# cookie.net
KiCad netlist of a schematic drawn in EAGLE
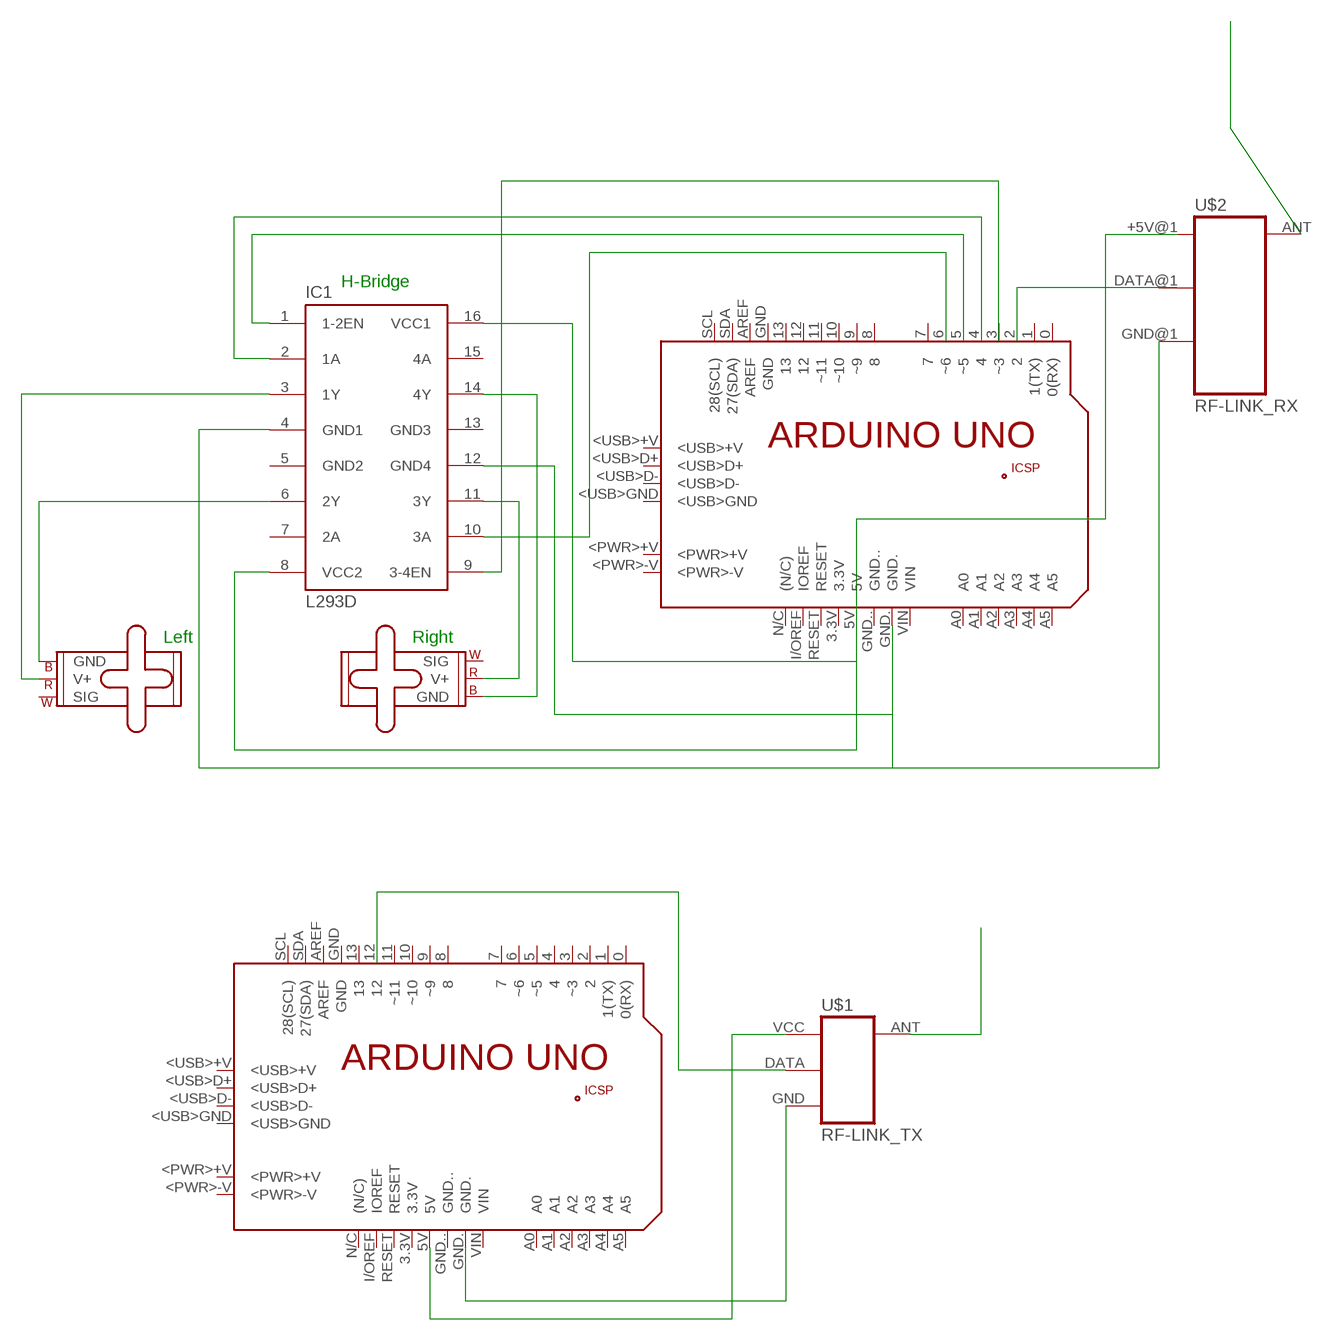
[diagram p0: schematic, sheet 1]

(export (version "E")
  (design (tool "Eeschema 10.0.6"))
  (components
    (comp (ref "IC1")
      (value "L293D")
      (footprint "eagle-import:DIL16")
      (libsource (lib "eagle-import") (part "L293D"))
    )
    (comp (ref "M1")
      (value "SMALL_SERVO")
      (footprint "eagle-import:1X03")
      (libsource (lib "eagle-import") (part "SMALL_SERVO"))
    )
    (comp (ref "M2")
      (value "SMALL_SERVO")
      (footprint "eagle-import:1X03")
      (libsource (lib "eagle-import") (part "SMALL_SERVO"))
    )
    (comp (ref "PCB1")
      (value "ARDUINO_UNO")
      (footprint "eagle-import:ARDUINO_UNO")
      (libsource (lib "eagle-import") (part "ARDUINO_UNO"))
    )
    (comp (ref "PCB2")
      (value "ARDUINO_UNO")
      (footprint "eagle-import:ARDUINO_UNO")
      (libsource (lib "eagle-import") (part "ARDUINO_UNO"))
    )
    (comp (ref "U$1")
      (value "RF-LINK_TX")
      (footprint "eagle-import:RF-LINK_TX")
      (libsource (lib "eagle-import") (part "RF-LINK_TX"))
    )
    (comp (ref "U$2")
      (value "RF-LINK_RX")
      (footprint "eagle-import:RF-LINK_RX")
      (libsource (lib "eagle-import") (part "RF-LINK_RX"))
    )
  )
  (nets
    (net (code "1") (name "/+5V") (class "Default")
      (node (ref "U$2") (pin "+5V@1") (pinfunction "+5V_+5V@1") (pintype "power_in"))
    )
    (net (code "2") (name "/GND2") (class "Default")
      (node (ref "IC1") (pin "5") (pinfunction "GND2_5") (pintype "power_in"))
    )
    (net (code "3") (name "/GND3") (class "Default")
      (node (ref "IC1") (pin "13") (pinfunction "GND3_13") (pintype "power_in"))
    )
    (net (code "4") (name "Net-(IC1-1Y)") (class "Default")
      (node (ref "IC1") (pin "3") (pinfunction "1Y_3") (pintype "output"))
      (node (ref "M1") (pin "2") (pinfunction "V+_2") (pintype "bidirectional"))
    )
    (net (code "5") (name "Net-(IC1-2Y)") (class "Default")
      (node (ref "IC1") (pin "6") (pinfunction "2Y_6") (pintype "output"))
      (node (ref "M1") (pin "3") (pinfunction "GND_3") (pintype "bidirectional"))
    )
    (net (code "6") (name "Net-(IC1-3Y)") (class "Default")
      (node (ref "IC1") (pin "11") (pinfunction "3Y_11") (pintype "output"))
      (node (ref "M2") (pin "2") (pinfunction "V+_2") (pintype "bidirectional"))
    )
    (net (code "7") (name "Net-(IC1-4Y)") (class "Default")
      (node (ref "IC1") (pin "14") (pinfunction "4Y_14") (pintype "output"))
      (node (ref "M2") (pin "3") (pinfunction "GND_3") (pintype "bidirectional"))
    )
    (net (code "8") (name "Net-(IC1-GND1)") (class "Default")
      (node (ref "IC1") (pin "12") (pinfunction "GND4_12") (pintype "power_in"))
      (node (ref "IC1") (pin "4") (pinfunction "GND1_4") (pintype "power_in"))
      (node (ref "PCB1") (pin "GND.") (pinfunction "GND._GND.") (pintype "bidirectional"))
      (node (ref "U$2") (pin "GND@1") (pinfunction "GND_GND@1") (pintype "power_in"))
    )
    (net (code "9") (name "Net-(IC1-VCC1)") (class "Default")
      (node (ref "IC1") (pin "16") (pinfunction "VCC1_16") (pintype "power_in"))
      (node (ref "IC1") (pin "8") (pinfunction "VCC2_8") (pintype "power_in"))
    )
    (net (code "10") (name "Net-(PCB2-PadGND.)") (class "Default")
      (node (ref "PCB2") (pin "GND.") (pinfunction "GND._GND.") (pintype "bidirectional"))
      (node (ref "U$1") (pin "GND") (pinfunction "GND_GND") (pintype "power_in"))
    )
    (net (code "11") (name "Net-(U$1-+5V)") (class "Default")
      (node (ref "PCB2") (pin "5V") (pinfunction "5V_5V") (pintype "bidirectional"))
      (node (ref "U$1") (pin "VCC") (pinfunction "+5V_VCC") (pintype "power_in"))
    )
    (net (code "12") (name "unconnected-(IC1-1-2EN-Pad1)") (class "Default")
      (node (ref "IC1") (pin "1") (pinfunction "1-2EN_1") (pintype "input"))
    )
    (net (code "13") (name "unconnected-(IC1-1A-Pad2)") (class "Default")
      (node (ref "IC1") (pin "2") (pinfunction "1A_2") (pintype "input"))
    )
    (net (code "14") (name "unconnected-(IC1-2A-Pad7)") (class "Default")
      (node (ref "IC1") (pin "7") (pinfunction "2A_7") (pintype "input"))
    )
    (net (code "15") (name "unconnected-(IC1-3-4EN-Pad9)") (class "Default")
      (node (ref "IC1") (pin "9") (pinfunction "3-4EN_9") (pintype "input"))
    )
    (net (code "16") (name "unconnected-(IC1-3A-Pad10)") (class "Default")
      (node (ref "IC1") (pin "10") (pinfunction "3A_10") (pintype "input"))
    )
    (net (code "17") (name "unconnected-(IC1-4A-Pad15)") (class "Default")
      (node (ref "IC1") (pin "15") (pinfunction "4A_15") (pintype "input"))
    )
    (net (code "18") (name "unconnected-(M1-SIG-Pad1)") (class "Default")
      (node (ref "M1") (pin "1") (pinfunction "SIG_1") (pintype "bidirectional"))
    )
    (net (code "19") (name "unconnected-(M2-SIG-Pad1)") (class "Default")
      (node (ref "M2") (pin "1") (pinfunction "SIG_1") (pintype "bidirectional"))
    )
    (net (code "20") (name "unconnected-(PCB1-(N{slash}C)-PadN{slash}C)") (class "Default")
      (node (ref "PCB1") (pin "N/C") (pinfunction "(N/C)_N/C") (pintype "bidirectional"))
    )
    (net (code "21") (name "unconnected-(PCB1-0(RX)-Pad0)") (class "Default")
      (node (ref "PCB1") (pin "0") (pinfunction "0(RX)_0") (pintype "bidirectional"))
    )
    (net (code "22") (name "unconnected-(PCB1-1(TX)-Pad1)") (class "Default")
      (node (ref "PCB1") (pin "1") (pinfunction "1(TX)_1") (pintype "bidirectional"))
    )
    (net (code "23") (name "unconnected-(PCB1-27(SDA)-PadSDA)") (class "Default")
      (node (ref "PCB1") (pin "SDA") (pinfunction "27(SDA)_SDA") (pintype "bidirectional"))
    )
    (net (code "24") (name "unconnected-(PCB1-28(SCL)-PadSCL)") (class "Default")
      (node (ref "PCB1") (pin "SCL") (pinfunction "28(SCL)_SCL") (pintype "bidirectional"))
    )
    (net (code "25") (name "unconnected-(PCB1-IOREF-PadI{slash}OREF)") (class "Default")
      (node (ref "PCB1") (pin "I/OREF") (pinfunction "IOREF_I/OREF") (pintype "bidirectional"))
    )
    (net (code "26") (name "unconnected-(PCB1-Pad+5V)") (class "Default")
      (node (ref "PCB1") (pin "+5V") (pinfunction "+5V_+5V") (pintype "bidirectional"))
    )
    (net (code "27") (name "unconnected-(PCB1-Pad2)") (class "Default")
      (node (ref "PCB1") (pin "2") (pinfunction "2_2") (pintype "bidirectional"))
    )
    (net (code "28") (name "unconnected-(PCB1-Pad3.3V)") (class "Default")
      (node (ref "PCB1") (pin "3.3V") (pinfunction "3.3V_3.3V") (pintype "bidirectional"))
    )
    (net (code "29") (name "unconnected-(PCB1-Pad4)") (class "Default")
      (node (ref "PCB1") (pin "4") (pinfunction "4_4") (pintype "bidirectional"))
    )
    (net (code "30") (name "unconnected-(PCB1-Pad5V)") (class "Default")
      (node (ref "PCB1") (pin "5V") (pinfunction "5V_5V") (pintype "bidirectional"))
    )
    (net (code "31") (name "unconnected-(PCB1-Pad7)") (class "Default")
      (node (ref "PCB1") (pin "7") (pinfunction "7_7") (pintype "bidirectional"))
    )
    (net (code "32") (name "unconnected-(PCB1-Pad8)") (class "Default")
      (node (ref "PCB1") (pin "8") (pinfunction "8_8") (pintype "bidirectional"))
    )
    (net (code "33") (name "unconnected-(PCB1-Pad12)") (class "Default")
      (node (ref "PCB1") (pin "12") (pinfunction "12_12") (pintype "bidirectional"))
    )
    (net (code "34") (name "unconnected-(PCB1-Pad13)") (class "Default")
      (node (ref "PCB1") (pin "13") (pinfunction "13_13") (pintype "bidirectional"))
    )
    (net (code "35") (name "unconnected-(PCB1-Pad<PWR>+V)") (class "Default")
      (node (ref "PCB1") (pin "<PWR>+V") (pinfunction "<PWR>+V_<PWR>+V") (pintype "bidirectional"))
    )
    (net (code "36") (name "unconnected-(PCB1-Pad<PWR>-V)") (class "Default")
      (node (ref "PCB1") (pin "<PWR>-V") (pinfunction "<PWR>-V_<PWR>-V") (pintype "bidirectional"))
    )
    (net (code "37") (name "unconnected-(PCB1-Pad<USB>+V)") (class "Default")
      (node (ref "PCB1") (pin "<USB>+V") (pinfunction "<USB>+V_<USB>+V") (pintype "bidirectional"))
    )
    (net (code "38") (name "unconnected-(PCB1-Pad<USB>D+)") (class "Default")
      (node (ref "PCB1") (pin "<USB>D+") (pinfunction "<USB>D+_<USB>D+") (pintype "bidirectional"))
    )
    (net (code "39") (name "unconnected-(PCB1-Pad<USB>D-)") (class "Default")
      (node (ref "PCB1") (pin "<USB>D-") (pinfunction "<USB>D-_<USB>D-") (pintype "bidirectional"))
    )
    (net (code "40") (name "unconnected-(PCB1-Pad<USB>GND)") (class "Default")
      (node (ref "PCB1") (pin "<USB>GND") (pinfunction "<USB>GND_<USB>GND") (pintype "bidirectional"))
    )
    (net (code "41") (name "unconnected-(PCB1-PadA0)") (class "Default")
      (node (ref "PCB1") (pin "A0") (pinfunction "A0_A0") (pintype "bidirectional"))
    )
    (net (code "42") (name "unconnected-(PCB1-PadA1)") (class "Default")
      (node (ref "PCB1") (pin "A1") (pinfunction "A1_A1") (pintype "bidirectional"))
    )
    (net (code "43") (name "unconnected-(PCB1-PadA2)") (class "Default")
      (node (ref "PCB1") (pin "A2") (pinfunction "A2_A2") (pintype "bidirectional"))
    )
    (net (code "44") (name "unconnected-(PCB1-PadA3)") (class "Default")
      (node (ref "PCB1") (pin "A3") (pinfunction "A3_A3") (pintype "bidirectional"))
    )
    (net (code "45") (name "unconnected-(PCB1-PadA4)") (class "Default")
      (node (ref "PCB1") (pin "A4") (pinfunction "A4_A4") (pintype "bidirectional"))
    )
    (net (code "46") (name "unconnected-(PCB1-PadA5)") (class "Default")
      (node (ref "PCB1") (pin "A5") (pinfunction "A5_A5") (pintype "bidirectional"))
    )
    (net (code "47") (name "unconnected-(PCB1-PadAREF)") (class "Default")
      (node (ref "PCB1") (pin "AREF") (pinfunction "AREF_AREF") (pintype "bidirectional"))
    )
    (net (code "48") (name "unconnected-(PCB1-PadGND)") (class "Default")
      (node (ref "PCB1") (pin "GND") (pinfunction "GND_GND") (pintype "bidirectional"))
    )
    (net (code "49") (name "unconnected-(PCB1-PadGND..)") (class "Default")
      (node (ref "PCB1") (pin "GND..") (pinfunction "GND.._GND..") (pintype "bidirectional"))
    )
    (net (code "50") (name "unconnected-(PCB1-PadGND_)") (class "Default")
      (node (ref "PCB1") (pin "GND_") (pinfunction "GND__GND_") (pintype "bidirectional"))
    )
    (net (code "51") (name "unconnected-(PCB1-PadMISO)") (class "Default")
      (node (ref "PCB1") (pin "MISO") (pinfunction "MISO_MISO") (pintype "bidirectional"))
    )
    (net (code "52") (name "unconnected-(PCB1-PadMOSI)") (class "Default")
      (node (ref "PCB1") (pin "MOSI") (pinfunction "MOSI_MOSI") (pintype "bidirectional"))
    )
    (net (code "53") (name "unconnected-(PCB1-PadRESET)") (class "Default")
      (node (ref "PCB1") (pin "RESET") (pinfunction "RESET_RESET") (pintype "bidirectional"))
    )
    (net (code "54") (name "unconnected-(PCB1-PadRESET.)") (class "Default")
      (node (ref "PCB1") (pin "RESET.") (pinfunction "RESET._RESET.") (pintype "bidirectional"))
    )
    (net (code "55") (name "unconnected-(PCB1-PadSCK)") (class "Default")
      (node (ref "PCB1") (pin "SCK") (pinfunction "SCK_SCK") (pintype "bidirectional"))
    )
    (net (code "56") (name "unconnected-(PCB1-PadVIN)") (class "Default")
      (node (ref "PCB1") (pin "VIN") (pinfunction "VIN_VIN") (pintype "bidirectional"))
    )
    (net (code "57") (name "unconnected-(PCB1-~{3}-Pad3)") (class "Default")
      (node (ref "PCB1") (pin "3") (pinfunction "~{3}_3") (pintype "bidirectional"))
    )
    (net (code "58") (name "unconnected-(PCB1-~{5}-Pad5)") (class "Default")
      (node (ref "PCB1") (pin "5") (pinfunction "~{5}_5") (pintype "bidirectional"))
    )
    (net (code "59") (name "unconnected-(PCB1-~{6}-Pad6)") (class "Default")
      (node (ref "PCB1") (pin "6") (pinfunction "~{6}_6") (pintype "bidirectional"))
    )
    (net (code "60") (name "unconnected-(PCB1-~{9}-Pad9)") (class "Default")
      (node (ref "PCB1") (pin "9") (pinfunction "~{9}_9") (pintype "bidirectional"))
    )
    (net (code "61") (name "unconnected-(PCB1-~{10}-Pad10)") (class "Default")
      (node (ref "PCB1") (pin "10") (pinfunction "~{10}_10") (pintype "bidirectional"))
    )
    (net (code "62") (name "unconnected-(PCB1-~{11}-Pad11)") (class "Default")
      (node (ref "PCB1") (pin "11") (pinfunction "~{11}_11") (pintype "bidirectional"))
    )
    (net (code "63") (name "unconnected-(PCB2-(N{slash}C)-PadN{slash}C)") (class "Default")
      (node (ref "PCB2") (pin "N/C") (pinfunction "(N/C)_N/C") (pintype "bidirectional"))
    )
    (net (code "64") (name "unconnected-(PCB2-0(RX)-Pad0)") (class "Default")
      (node (ref "PCB2") (pin "0") (pinfunction "0(RX)_0") (pintype "bidirectional"))
    )
    (net (code "65") (name "unconnected-(PCB2-1(TX)-Pad1)") (class "Default")
      (node (ref "PCB2") (pin "1") (pinfunction "1(TX)_1") (pintype "bidirectional"))
    )
    (net (code "66") (name "unconnected-(PCB2-27(SDA)-PadSDA)") (class "Default")
      (node (ref "PCB2") (pin "SDA") (pinfunction "27(SDA)_SDA") (pintype "bidirectional"))
    )
    (net (code "67") (name "unconnected-(PCB2-28(SCL)-PadSCL)") (class "Default")
      (node (ref "PCB2") (pin "SCL") (pinfunction "28(SCL)_SCL") (pintype "bidirectional"))
    )
    (net (code "68") (name "unconnected-(PCB2-IOREF-PadI{slash}OREF)") (class "Default")
      (node (ref "PCB2") (pin "I/OREF") (pinfunction "IOREF_I/OREF") (pintype "bidirectional"))
    )
    (net (code "69") (name "unconnected-(PCB2-Pad+5V)") (class "Default")
      (node (ref "PCB2") (pin "+5V") (pinfunction "+5V_+5V") (pintype "bidirectional"))
    )
    (net (code "70") (name "unconnected-(PCB2-Pad2)") (class "Default")
      (node (ref "PCB2") (pin "2") (pinfunction "2_2") (pintype "bidirectional"))
    )
    (net (code "71") (name "unconnected-(PCB2-Pad3.3V)") (class "Default")
      (node (ref "PCB2") (pin "3.3V") (pinfunction "3.3V_3.3V") (pintype "bidirectional"))
    )
    (net (code "72") (name "unconnected-(PCB2-Pad4)") (class "Default")
      (node (ref "PCB2") (pin "4") (pinfunction "4_4") (pintype "bidirectional"))
    )
    (net (code "73") (name "unconnected-(PCB2-Pad7)") (class "Default")
      (node (ref "PCB2") (pin "7") (pinfunction "7_7") (pintype "bidirectional"))
    )
    (net (code "74") (name "unconnected-(PCB2-Pad8)") (class "Default")
      (node (ref "PCB2") (pin "8") (pinfunction "8_8") (pintype "bidirectional"))
    )
    (net (code "75") (name "unconnected-(PCB2-Pad12)") (class "Default")
      (node (ref "PCB2") (pin "12") (pinfunction "12_12") (pintype "bidirectional"))
    )
    (net (code "76") (name "unconnected-(PCB2-Pad13)") (class "Default")
      (node (ref "PCB2") (pin "13") (pinfunction "13_13") (pintype "bidirectional"))
    )
    (net (code "77") (name "unconnected-(PCB2-Pad<PWR>+V)") (class "Default")
      (node (ref "PCB2") (pin "<PWR>+V") (pinfunction "<PWR>+V_<PWR>+V") (pintype "bidirectional"))
    )
    (net (code "78") (name "unconnected-(PCB2-Pad<PWR>-V)") (class "Default")
      (node (ref "PCB2") (pin "<PWR>-V") (pinfunction "<PWR>-V_<PWR>-V") (pintype "bidirectional"))
    )
    (net (code "79") (name "unconnected-(PCB2-Pad<USB>+V)") (class "Default")
      (node (ref "PCB2") (pin "<USB>+V") (pinfunction "<USB>+V_<USB>+V") (pintype "bidirectional"))
    )
    (net (code "80") (name "unconnected-(PCB2-Pad<USB>D+)") (class "Default")
      (node (ref "PCB2") (pin "<USB>D+") (pinfunction "<USB>D+_<USB>D+") (pintype "bidirectional"))
    )
    (net (code "81") (name "unconnected-(PCB2-Pad<USB>D-)") (class "Default")
      (node (ref "PCB2") (pin "<USB>D-") (pinfunction "<USB>D-_<USB>D-") (pintype "bidirectional"))
    )
    (net (code "82") (name "unconnected-(PCB2-Pad<USB>GND)") (class "Default")
      (node (ref "PCB2") (pin "<USB>GND") (pinfunction "<USB>GND_<USB>GND") (pintype "bidirectional"))
    )
    (net (code "83") (name "unconnected-(PCB2-PadA0)") (class "Default")
      (node (ref "PCB2") (pin "A0") (pinfunction "A0_A0") (pintype "bidirectional"))
    )
    (net (code "84") (name "unconnected-(PCB2-PadA1)") (class "Default")
      (node (ref "PCB2") (pin "A1") (pinfunction "A1_A1") (pintype "bidirectional"))
    )
    (net (code "85") (name "unconnected-(PCB2-PadA2)") (class "Default")
      (node (ref "PCB2") (pin "A2") (pinfunction "A2_A2") (pintype "bidirectional"))
    )
    (net (code "86") (name "unconnected-(PCB2-PadA3)") (class "Default")
      (node (ref "PCB2") (pin "A3") (pinfunction "A3_A3") (pintype "bidirectional"))
    )
    (net (code "87") (name "unconnected-(PCB2-PadA4)") (class "Default")
      (node (ref "PCB2") (pin "A4") (pinfunction "A4_A4") (pintype "bidirectional"))
    )
    (net (code "88") (name "unconnected-(PCB2-PadA5)") (class "Default")
      (node (ref "PCB2") (pin "A5") (pinfunction "A5_A5") (pintype "bidirectional"))
    )
    (net (code "89") (name "unconnected-(PCB2-PadAREF)") (class "Default")
      (node (ref "PCB2") (pin "AREF") (pinfunction "AREF_AREF") (pintype "bidirectional"))
    )
    (net (code "90") (name "unconnected-(PCB2-PadGND)") (class "Default")
      (node (ref "PCB2") (pin "GND") (pinfunction "GND_GND") (pintype "bidirectional"))
    )
    (net (code "91") (name "unconnected-(PCB2-PadGND..)") (class "Default")
      (node (ref "PCB2") (pin "GND..") (pinfunction "GND.._GND..") (pintype "bidirectional"))
    )
    (net (code "92") (name "unconnected-(PCB2-PadGND_)") (class "Default")
      (node (ref "PCB2") (pin "GND_") (pinfunction "GND__GND_") (pintype "bidirectional"))
    )
    (net (code "93") (name "unconnected-(PCB2-PadMISO)") (class "Default")
      (node (ref "PCB2") (pin "MISO") (pinfunction "MISO_MISO") (pintype "bidirectional"))
    )
    (net (code "94") (name "unconnected-(PCB2-PadMOSI)") (class "Default")
      (node (ref "PCB2") (pin "MOSI") (pinfunction "MOSI_MOSI") (pintype "bidirectional"))
    )
    (net (code "95") (name "unconnected-(PCB2-PadRESET)") (class "Default")
      (node (ref "PCB2") (pin "RESET") (pinfunction "RESET_RESET") (pintype "bidirectional"))
    )
    (net (code "96") (name "unconnected-(PCB2-PadRESET.)") (class "Default")
      (node (ref "PCB2") (pin "RESET.") (pinfunction "RESET._RESET.") (pintype "bidirectional"))
    )
    (net (code "97") (name "unconnected-(PCB2-PadSCK)") (class "Default")
      (node (ref "PCB2") (pin "SCK") (pinfunction "SCK_SCK") (pintype "bidirectional"))
    )
    (net (code "98") (name "unconnected-(PCB2-PadVIN)") (class "Default")
      (node (ref "PCB2") (pin "VIN") (pinfunction "VIN_VIN") (pintype "bidirectional"))
    )
    (net (code "99") (name "unconnected-(PCB2-~{3}-Pad3)") (class "Default")
      (node (ref "PCB2") (pin "3") (pinfunction "~{3}_3") (pintype "bidirectional"))
    )
    (net (code "100") (name "unconnected-(PCB2-~{5}-Pad5)") (class "Default")
      (node (ref "PCB2") (pin "5") (pinfunction "~{5}_5") (pintype "bidirectional"))
    )
    (net (code "101") (name "unconnected-(PCB2-~{6}-Pad6)") (class "Default")
      (node (ref "PCB2") (pin "6") (pinfunction "~{6}_6") (pintype "bidirectional"))
    )
    (net (code "102") (name "unconnected-(PCB2-~{9}-Pad9)") (class "Default")
      (node (ref "PCB2") (pin "9") (pinfunction "~{9}_9") (pintype "bidirectional"))
    )
    (net (code "103") (name "unconnected-(PCB2-~{10}-Pad10)") (class "Default")
      (node (ref "PCB2") (pin "10") (pinfunction "~{10}_10") (pintype "bidirectional"))
    )
    (net (code "104") (name "unconnected-(PCB2-~{11}-Pad11)") (class "Default")
      (node (ref "PCB2") (pin "11") (pinfunction "~{11}_11") (pintype "bidirectional"))
    )
    (net (code "105") (name "unconnected-(U$1-PadANT)") (class "Default")
      (node (ref "U$1") (pin "ANT") (pinfunction "ANT_ANT") (pintype "passive"))
    )
    (net (code "106") (name "unconnected-(U$1-PadDATA)") (class "Default")
      (node (ref "U$1") (pin "DATA") (pinfunction "DATA_DATA") (pintype "input"))
    )
    (net (code "107") (name "unconnected-(U$2-DATA-PadDATA@1)") (class "Default")
      (node (ref "U$2") (pin "DATA@1") (pinfunction "DATA_DATA@1") (pintype "input"))
    )
    (net (code "108") (name "unconnected-(U$2-PadANT)") (class "Default")
      (node (ref "U$2") (pin "ANT") (pinfunction "ANT_ANT") (pintype "passive"))
    )
  )
)
